# fonte.net
KiCad netlist of a schematic drawn in EAGLE
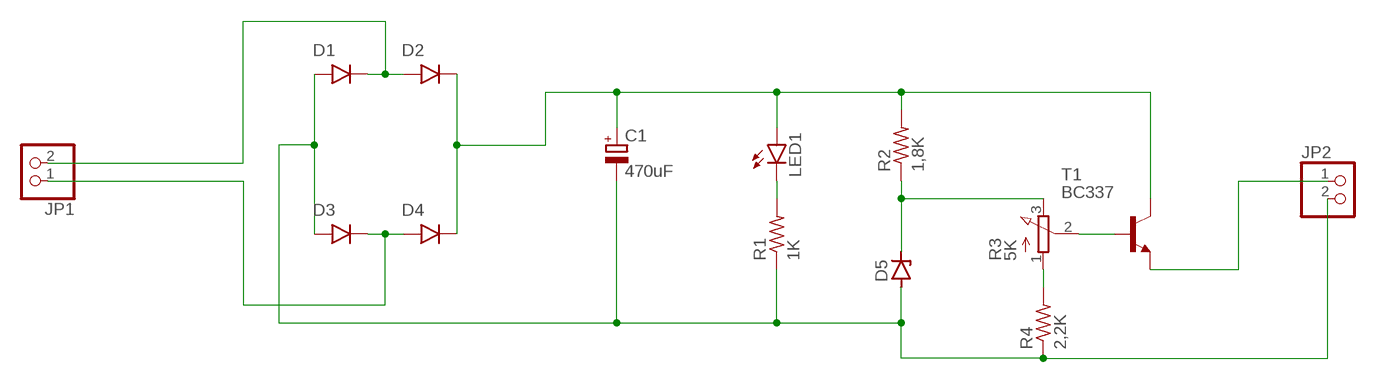
[diagram p0: schematic, sheet 1]

(export (version "E")
  (design (tool "Eeschema 10.0.6"))
  (components
    (comp (ref "C1")
      (value "470uF")
      (footprint "eagle-import:E3,5-10")
      (libsource (lib "eagle-import") (part "CPOL-EUE3.5-10"))
    )
    (comp (ref "D1")
      (value "1N4001")
      (footprint "eagle-import:DO41-10")
      (libsource (lib "eagle-import") (part "1N4001"))
    )
    (comp (ref "D2")
      (value "1N4001")
      (footprint "eagle-import:DO41-10")
      (libsource (lib "eagle-import") (part "1N4001"))
    )
    (comp (ref "D3")
      (value "1N4001")
      (footprint "eagle-import:DO41-10")
      (libsource (lib "eagle-import") (part "1N4001"))
    )
    (comp (ref "D4")
      (value "1N4001")
      (footprint "eagle-import:DO41-10")
      (libsource (lib "eagle-import") (part "1N4001"))
    )
    (comp (ref "D5")
      (value "ZENER-DIODEDO34-7")
      (footprint "eagle-import:DO34Z7")
      (libsource (lib "eagle-import") (part "ZENER-DIODEDO34-7"))
    )
    (comp (ref "JP1")
      (value "PINHD-1X2")
      (footprint "eagle-import:1X02")
      (libsource (lib "eagle-import") (part "PINHD-1X2"))
    )
    (comp (ref "JP2")
      (value "PINHD-1X2")
      (footprint "eagle-import:1X02")
      (libsource (lib "eagle-import") (part "PINHD-1X2"))
    )
    (comp (ref "LED1")
      (value "LED5MM")
      (footprint "eagle-import:LED5MM")
      (libsource (lib "eagle-import") (part "LED5MM"))
    )
    (comp (ref "R1")
      (value "1K")
      (footprint "eagle-import:0309_12")
      (libsource (lib "eagle-import") (part "R-US_0309/12"))
    )
    (comp (ref "R2")
      (value "1,8K")
      (footprint "eagle-import:0309_12")
      (libsource (lib "eagle-import") (part "R-US_0309/12"))
    )
    (comp (ref "R3")
      (value "5K")
      (footprint "eagle-import:3RP_1610N")
      (libsource (lib "eagle-import") (part "3RP/1610N"))
    )
    (comp (ref "R4")
      (value "2,2K")
      (footprint "eagle-import:0309_12")
      (libsource (lib "eagle-import") (part "R-US_0309/12"))
    )
    (comp (ref "T1")
      (value "BC337")
      (footprint "eagle-import:TO92")
      (libsource (lib "eagle-import") (part "BC337"))
    )
  )
  (nets
    (net (code "1") (name "Net-(D1-ANODE)") (class "Default")
      (node (ref "C1") (pin "-") (pinfunction "-_-") (pintype "passive"))
      (node (ref "D1") (pin "A") (pinfunction "ANODE_A") (pintype "passive"))
      (node (ref "D3") (pin "A") (pinfunction "ANODE_A") (pintype "passive"))
      (node (ref "D5") (pin "A") (pinfunction "A_A") (pintype "passive"))
      (node (ref "JP2") (pin "2") (pinfunction "2_2") (pintype "passive"))
      (node (ref "R1") (pin "1") (pinfunction "1_1") (pintype "passive"))
      (node (ref "R4") (pin "1") (pinfunction "1_1") (pintype "passive"))
    )
    (net (code "2") (name "Net-(D1-CATHODE)") (class "Default")
      (node (ref "D1") (pin "C") (pinfunction "CATHODE_C") (pintype "passive"))
      (node (ref "D2") (pin "A") (pinfunction "ANODE_A") (pintype "passive"))
      (node (ref "JP1") (pin "2") (pinfunction "2_2") (pintype "passive"))
    )
    (net (code "3") (name "Net-(D2-CATHODE)") (class "Default")
      (node (ref "C1") (pin "+") (pinfunction "+_+") (pintype "passive"))
      (node (ref "D2") (pin "C") (pinfunction "CATHODE_C") (pintype "passive"))
      (node (ref "D4") (pin "C") (pinfunction "CATHODE_C") (pintype "passive"))
      (node (ref "LED1") (pin "A") (pinfunction "A_A") (pintype "passive"))
      (node (ref "R2") (pin "2") (pinfunction "2_2") (pintype "passive"))
      (node (ref "T1") (pin "3") (pinfunction "C_3") (pintype "passive"))
    )
    (net (code "4") (name "Net-(D3-CATHODE)") (class "Default")
      (node (ref "D3") (pin "C") (pinfunction "CATHODE_C") (pintype "passive"))
      (node (ref "D4") (pin "A") (pinfunction "ANODE_A") (pintype "passive"))
      (node (ref "JP1") (pin "1") (pinfunction "1_1") (pintype "passive"))
    )
    (net (code "5") (name "Net-(LED1-C)") (class "Default")
      (node (ref "LED1") (pin "K") (pinfunction "C_K") (pintype "passive"))
      (node (ref "R1") (pin "2") (pinfunction "2_2") (pintype "passive"))
    )
    (net (code "6") (name "Net-(R3-A)") (class "Default")
      (node (ref "R3") (pin "1") (pinfunction "A_1") (pintype "passive"))
      (node (ref "R4") (pin "2") (pinfunction "2_2") (pintype "passive"))
    )
    (net (code "7") (name "Net-(R3-E)") (class "Default")
      (node (ref "D5") (pin "C") (pinfunction "C_C") (pintype "passive"))
      (node (ref "R2") (pin "1") (pinfunction "1_1") (pintype "passive"))
      (node (ref "R3") (pin "3") (pinfunction "E_3") (pintype "passive"))
    )
    (net (code "8") (name "Net-(R3-S)") (class "Default")
      (node (ref "R3") (pin "2") (pinfunction "S_2") (pintype "passive"))
      (node (ref "T1") (pin "2") (pinfunction "B_2") (pintype "passive"))
    )
    (net (code "9") (name "Net-(T1-E)") (class "Default")
      (node (ref "JP2") (pin "1") (pinfunction "1_1") (pintype "passive"))
      (node (ref "T1") (pin "1") (pinfunction "E_1") (pintype "passive"))
    )
  )
)
